# projekt.net
KiCad netlist of a schematic drawn in EAGLE
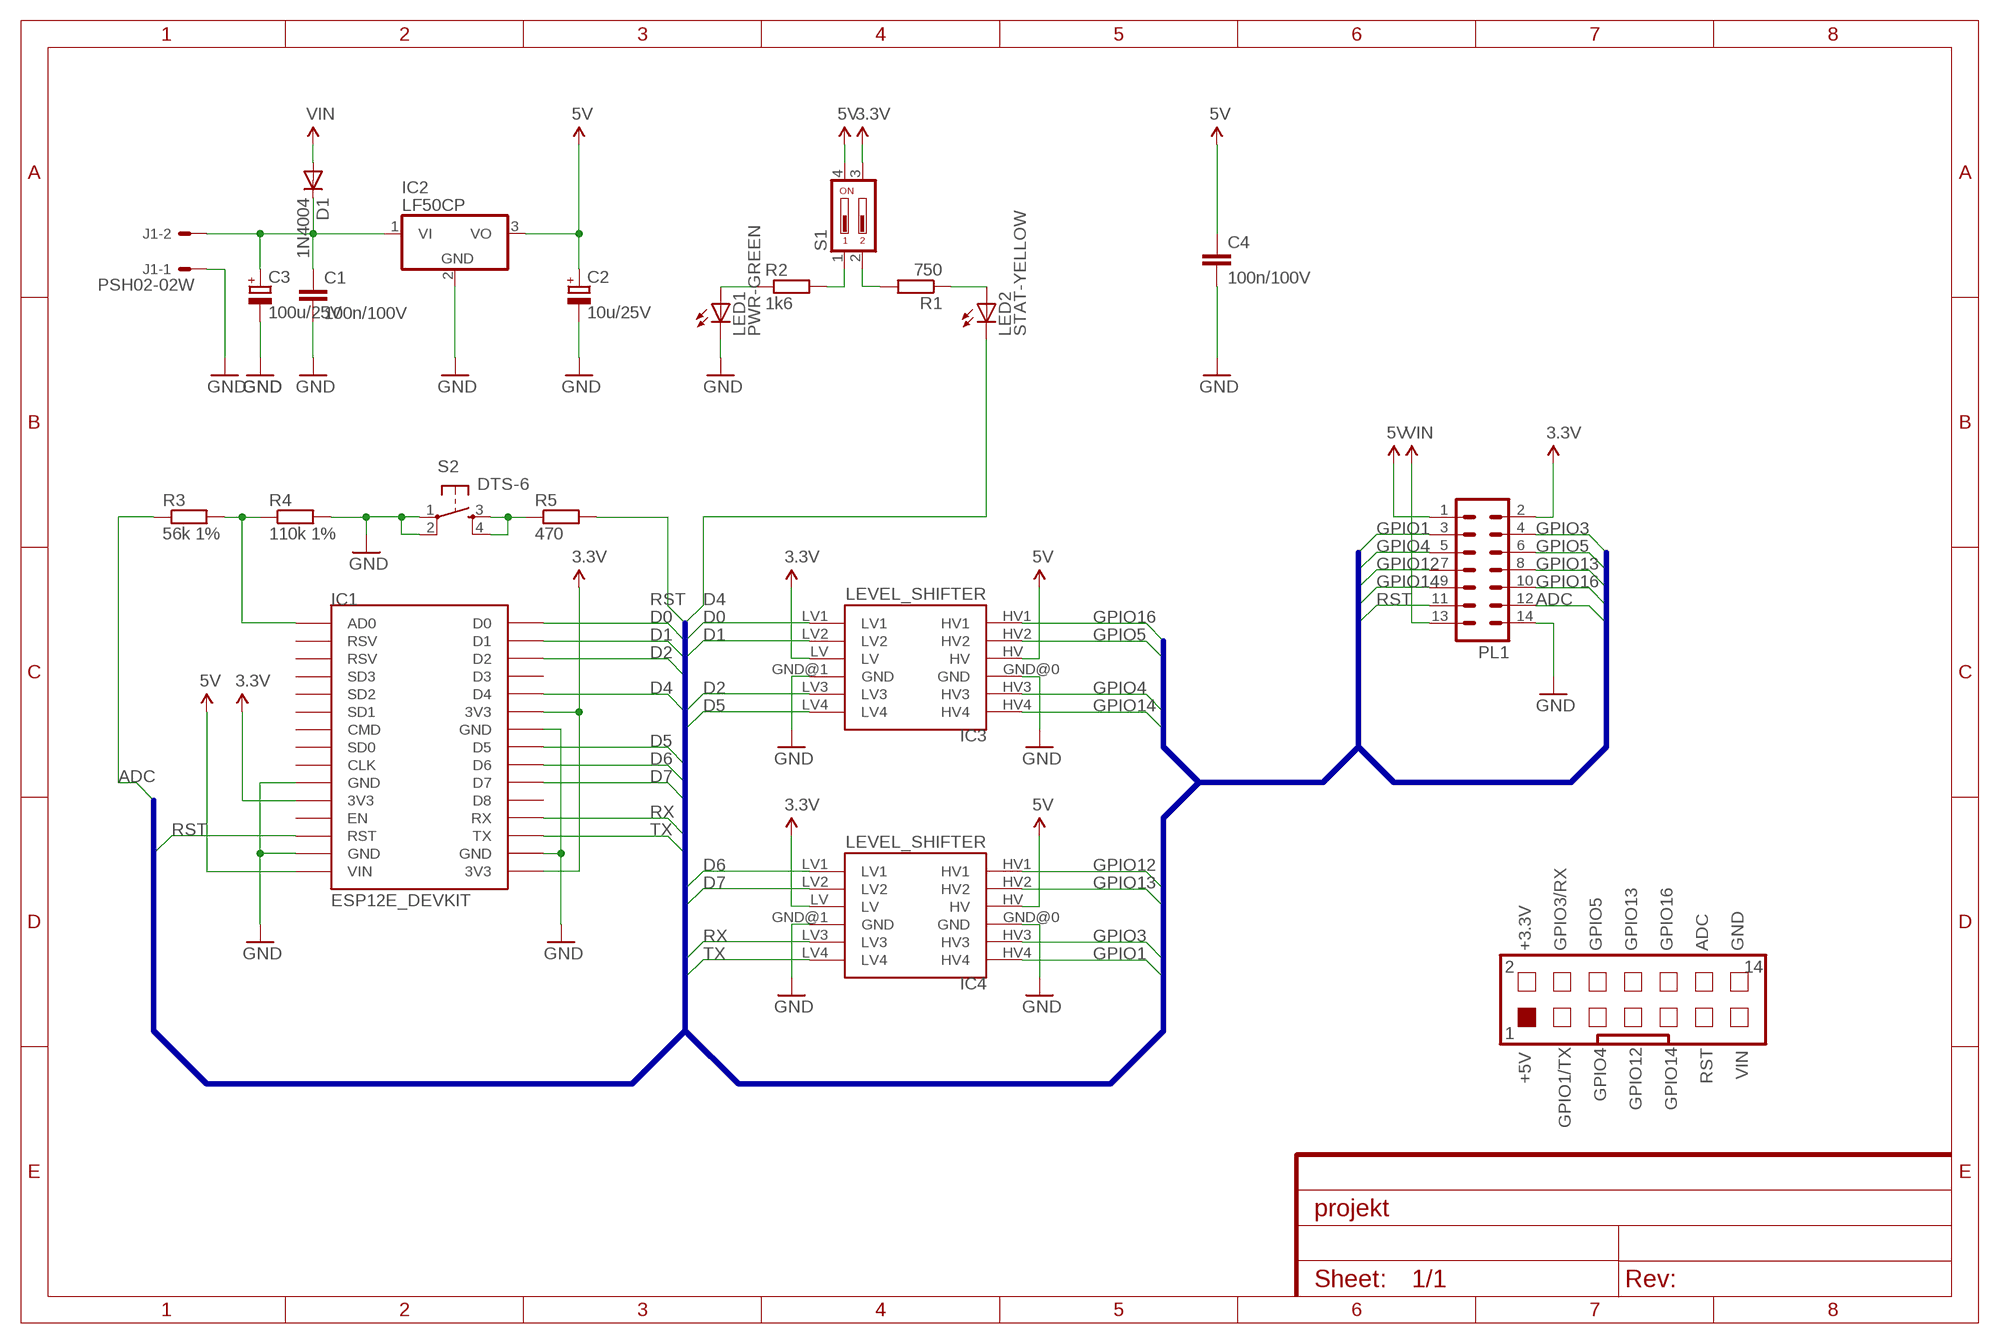
[diagram p0: schematic, sheet 1]

(export (version "E")
  (design (tool "Eeschema 10.0.6"))
  (components
    (comp (ref "C1")
      (value "100n/100V")
      (footprint "eagle-import:C025-025X050")
      (libsource (lib "eagle-import") (part "C-EUC025-025X050"))
    )
    (comp (ref "C2")
      (value "10u/25V")
      (footprint "eagle-import:E3,5-8")
      (libsource (lib "eagle-import") (part "CPOL-EUE3,5-8"))
    )
    (comp (ref "C3")
      (value "100u/25V")
      (footprint "eagle-import:E5-13")
      (libsource (lib "eagle-import") (part "CPOL-EUE5-13"))
    )
    (comp (ref "C4")
      (value "100n/100V")
      (footprint "eagle-import:C025-025X050")
      (libsource (lib "eagle-import") (part "C-EUC025-025X050"))
    )
    (comp (ref "D1")
      (value "1N4004")
      (footprint "eagle-import:DO41-10")
      (libsource (lib "eagle-import") (part "1N4004"))
    )
    (comp (ref "IC1")
      (value "ESP12E_DEVKIT")
      (footprint "eagle-import:ESP12E_DEVKIT")
      (libsource (lib "eagle-import") (part "ESP12E_DEVKIT"))
    )
    (comp (ref "IC2")
      (value "LF50CP")
      (footprint "eagle-import:TO220H")
      (libsource (lib "eagle-import") (part "LF50CP"))
    )
    (comp (ref "IC3")
      (value "LEVEL_SHIFTER")
      (footprint "eagle-import:LEVEL_SHIFTER")
      (libsource (lib "eagle-import") (part "LEVEL_SHIFTER"))
    )
    (comp (ref "IC4")
      (value "LEVEL_SHIFTER")
      (footprint "eagle-import:LEVEL_SHIFTER")
      (libsource (lib "eagle-import") (part "LEVEL_SHIFTER"))
    )
    (comp (ref "J1")
      (value "PSH02-02W")
      (footprint "eagle-import:7395-02")
      (libsource (lib "eagle-import") (part "22-?-0205-7028"))
    )
    (comp (ref "LED1")
      (value "PWR-GREEN")
      (footprint "eagle-import:LED3MM")
      (libsource (lib "eagle-import") (part "LED3MM"))
    )
    (comp (ref "LED2")
      (value "STAT-YELLOW")
      (footprint "eagle-import:LED3MM")
      (libsource (lib "eagle-import") (part "LED3MM"))
    )
    (comp (ref "PL1")
      (value "14H")
      (footprint "eagle-import:14H")
      (libsource (lib "eagle-import") (part "14H"))
    )
    (comp (ref "R1")
      (value "750")
      (footprint "eagle-import:R1206")
      (libsource (lib "eagle-import") (part "R-EU_R1206"))
    )
    (comp (ref "R2")
      (value "1k6")
      (footprint "eagle-import:R1206")
      (libsource (lib "eagle-import") (part "R-EU_R1206"))
    )
    (comp (ref "R3")
      (value "56k 1%")
      (footprint "eagle-import:R1206")
      (libsource (lib "eagle-import") (part "R-EU_R1206"))
    )
    (comp (ref "R4")
      (value "110k 1%")
      (footprint "eagle-import:R1206")
      (libsource (lib "eagle-import") (part "R-EU_R1206"))
    )
    (comp (ref "R5")
      (value "470")
      (footprint "eagle-import:R1206")
      (libsource (lib "eagle-import") (part "R-EU_R1206"))
    )
    (comp (ref "S1")
      (value "DIP02YL")
      (footprint "eagle-import:DIP02YL")
      (libsource (lib "eagle-import") (part "DIP02YL"))
    )
    (comp (ref "S2")
      (value "DTS-6")
      (footprint "eagle-import:DTS-6")
      (libsource (lib "eagle-import") (part "DTS-6"))
    )
  )
  (nets
    (net (code "1") (name "/ADC") (class "Default")
      (node (ref "PL1") (pin "12") (pinfunction "12_12") (pintype "passive"))
      (node (ref "R3") (pin "1") (pinfunction "1_1") (pintype "passive"))
    )
    (net (code "2") (name "/D0") (class "Default")
      (node (ref "IC1") (pin "D0") (pinfunction "D0_D0") (pintype "bidirectional"))
      (node (ref "IC3") (pin "LV1") (pinfunction "LV1_LV1") (pintype "bidirectional"))
    )
    (net (code "3") (name "/D1") (class "Default")
      (node (ref "IC1") (pin "D1") (pinfunction "D1_D1") (pintype "bidirectional"))
      (node (ref "IC3") (pin "LV2") (pinfunction "LV2_LV2") (pintype "bidirectional"))
    )
    (net (code "4") (name "/D2") (class "Default")
      (node (ref "IC1") (pin "D2") (pinfunction "D2_D2") (pintype "bidirectional"))
      (node (ref "IC3") (pin "LV3") (pinfunction "LV3_LV3") (pintype "bidirectional"))
    )
    (net (code "5") (name "/D4") (class "Default")
      (node (ref "IC1") (pin "D4") (pinfunction "D4_D4") (pintype "bidirectional"))
      (node (ref "LED2") (pin "K") (pinfunction "C_K") (pintype "passive"))
    )
    (net (code "6") (name "/D5") (class "Default")
      (node (ref "IC1") (pin "D5") (pinfunction "D5_D5") (pintype "bidirectional"))
      (node (ref "IC3") (pin "LV4") (pinfunction "LV4_LV4") (pintype "bidirectional"))
    )
    (net (code "7") (name "/D6") (class "Default")
      (node (ref "IC1") (pin "D6") (pinfunction "D6_D6") (pintype "bidirectional"))
      (node (ref "IC4") (pin "LV1") (pinfunction "LV1_LV1") (pintype "bidirectional"))
    )
    (net (code "8") (name "/D7") (class "Default")
      (node (ref "IC1") (pin "D7") (pinfunction "D7_D7") (pintype "bidirectional"))
      (node (ref "IC4") (pin "LV2") (pinfunction "LV2_LV2") (pintype "bidirectional"))
    )
    (net (code "9") (name "/GPIO1") (class "Default")
      (node (ref "IC4") (pin "HV4") (pinfunction "HV4_HV4") (pintype "bidirectional"))
      (node (ref "PL1") (pin "3") (pinfunction "3_3") (pintype "passive"))
    )
    (net (code "10") (name "/GPIO3") (class "Default")
      (node (ref "IC4") (pin "HV3") (pinfunction "HV3_HV3") (pintype "bidirectional"))
      (node (ref "PL1") (pin "4") (pinfunction "4_4") (pintype "passive"))
    )
    (net (code "11") (name "/GPIO4") (class "Default")
      (node (ref "IC3") (pin "HV3") (pinfunction "HV3_HV3") (pintype "bidirectional"))
      (node (ref "PL1") (pin "5") (pinfunction "5_5") (pintype "passive"))
    )
    (net (code "12") (name "/GPIO5") (class "Default")
      (node (ref "IC3") (pin "HV2") (pinfunction "HV2_HV2") (pintype "bidirectional"))
      (node (ref "PL1") (pin "6") (pinfunction "6_6") (pintype "passive"))
    )
    (net (code "13") (name "/GPIO12") (class "Default")
      (node (ref "IC4") (pin "HV1") (pinfunction "HV1_HV1") (pintype "bidirectional"))
      (node (ref "PL1") (pin "7") (pinfunction "7_7") (pintype "passive"))
    )
    (net (code "14") (name "/GPIO13") (class "Default")
      (node (ref "IC4") (pin "HV2") (pinfunction "HV2_HV2") (pintype "bidirectional"))
      (node (ref "PL1") (pin "8") (pinfunction "8_8") (pintype "passive"))
    )
    (net (code "15") (name "/GPIO14") (class "Default")
      (node (ref "IC3") (pin "HV4") (pinfunction "HV4_HV4") (pintype "bidirectional"))
      (node (ref "PL1") (pin "9") (pinfunction "9_9") (pintype "passive"))
    )
    (net (code "16") (name "/GPIO16") (class "Default")
      (node (ref "IC3") (pin "HV1") (pinfunction "HV1_HV1") (pintype "bidirectional"))
      (node (ref "PL1") (pin "10") (pinfunction "10_10") (pintype "passive"))
    )
    (net (code "17") (name "/RST") (class "Default")
      (node (ref "IC1") (pin "RST") (pinfunction "RST_RST") (pintype "bidirectional"))
      (node (ref "PL1") (pin "11") (pinfunction "11_11") (pintype "passive"))
      (node (ref "R5") (pin "2") (pinfunction "2_2") (pintype "passive"))
    )
    (net (code "18") (name "/RX") (class "Default")
      (node (ref "IC1") (pin "RX") (pinfunction "RX_RX") (pintype "bidirectional"))
      (node (ref "IC4") (pin "LV3") (pinfunction "LV3_LV3") (pintype "bidirectional"))
    )
    (net (code "19") (name "/TX") (class "Default")
      (node (ref "IC1") (pin "TX") (pinfunction "TX_TX") (pintype "bidirectional"))
      (node (ref "IC4") (pin "LV4") (pinfunction "LV4_LV4") (pintype "bidirectional"))
    )
    (net (code "20") (name "3.3V") (class "Default")
      (node (ref "IC1") (pin "3V3@0") (pinfunction "3V3_3V3@0") (pintype "bidirectional"))
      (node (ref "IC1") (pin "3V3@1") (pinfunction "3V3_3V3@1") (pintype "bidirectional"))
      (node (ref "IC1") (pin "3V3@2") (pinfunction "3V3_3V3@2") (pintype "bidirectional"))
      (node (ref "IC3") (pin "LV") (pinfunction "LV_LV") (pintype "bidirectional"))
      (node (ref "IC4") (pin "LV") (pinfunction "LV_LV") (pintype "bidirectional"))
      (node (ref "PL1") (pin "2") (pinfunction "2_2") (pintype "passive"))
      (node (ref "S1") (pin "3") (pinfunction "3_3") (pintype "passive"))
    )
    (net (code "21") (name "5V") (class "Default")
      (node (ref "C2") (pin "+") (pinfunction "+_+") (pintype "passive"))
      (node (ref "C4") (pin "1") (pinfunction "1_1") (pintype "passive"))
      (node (ref "IC1") (pin "VIN") (pinfunction "VIN_VIN") (pintype "bidirectional"))
      (node (ref "IC2") (pin "3") (pinfunction "VO_3") (pintype "passive"))
      (node (ref "IC3") (pin "HV") (pinfunction "HV_HV") (pintype "bidirectional"))
      (node (ref "IC4") (pin "HV") (pinfunction "HV_HV") (pintype "bidirectional"))
      (node (ref "PL1") (pin "1") (pinfunction "1_1") (pintype "passive"))
      (node (ref "S1") (pin "4") (pinfunction "4_4") (pintype "passive"))
    )
    (net (code "22") (name "GND") (class "Default")
      (node (ref "C1") (pin "2") (pinfunction "2_2") (pintype "passive"))
      (node (ref "C2") (pin "-") (pinfunction "-_-") (pintype "passive"))
      (node (ref "C3") (pin "-") (pinfunction "-_-") (pintype "passive"))
      (node (ref "C4") (pin "2") (pinfunction "2_2") (pintype "passive"))
      (node (ref "IC1") (pin "GND@0") (pinfunction "GND_GND@0") (pintype "bidirectional"))
      (node (ref "IC1") (pin "GND@1") (pinfunction "GND_GND@1") (pintype "bidirectional"))
      (node (ref "IC1") (pin "GND@2") (pinfunction "GND_GND@2") (pintype "bidirectional"))
      (node (ref "IC1") (pin "GND@3") (pinfunction "GND_GND@3") (pintype "bidirectional"))
      (node (ref "IC2") (pin "2") (pinfunction "GND_2") (pintype "passive"))
      (node (ref "IC3") (pin "GND@0") (pinfunction "GND_GND@0") (pintype "bidirectional"))
      (node (ref "IC3") (pin "GND@1") (pinfunction "GND_GND@1") (pintype "bidirectional"))
      (node (ref "IC4") (pin "GND@0") (pinfunction "GND_GND@0") (pintype "bidirectional"))
      (node (ref "IC4") (pin "GND@1") (pinfunction "GND_GND@1") (pintype "bidirectional"))
      (node (ref "J1") (pin "1") (pinfunction "S_1") (pintype "passive"))
      (node (ref "LED1") (pin "K") (pinfunction "C_K") (pintype "passive"))
      (node (ref "PL1") (pin "14") (pinfunction "14_14") (pintype "passive"))
      (node (ref "R4") (pin "2") (pinfunction "2_2") (pintype "passive"))
      (node (ref "S2") (pin "1") (pinfunction "1_1") (pintype "passive"))
      (node (ref "S2") (pin "2") (pinfunction "2_2") (pintype "passive"))
    )
    (net (code "23") (name "Net-(IC1-PadAD0)") (class "Default")
      (node (ref "IC1") (pin "AD0") (pinfunction "AD0_AD0") (pintype "bidirectional"))
      (node (ref "R3") (pin "2") (pinfunction "2_2") (pintype "passive"))
      (node (ref "R4") (pin "1") (pinfunction "1_1") (pintype "passive"))
    )
    (net (code "24") (name "Net-(IC2-VI)") (class "Default")
      (node (ref "C1") (pin "1") (pinfunction "1_1") (pintype "passive"))
      (node (ref "C3") (pin "+") (pinfunction "+_+") (pintype "passive"))
      (node (ref "D1") (pin "C") (pinfunction "C_C") (pintype "passive"))
      (node (ref "IC2") (pin "1") (pinfunction "VI_1") (pintype "input"))
      (node (ref "J1") (pin "2") (pinfunction "S_2") (pintype "passive"))
    )
    (net (code "25") (name "Net-(LED1-PadA)") (class "Default")
      (node (ref "LED1") (pin "A") (pinfunction "A_A") (pintype "passive"))
      (node (ref "R2") (pin "1") (pinfunction "1_1") (pintype "passive"))
    )
    (net (code "26") (name "Net-(LED2-PadA)") (class "Default")
      (node (ref "LED2") (pin "A") (pinfunction "A_A") (pintype "passive"))
      (node (ref "R1") (pin "1") (pinfunction "1_1") (pintype "passive"))
    )
    (net (code "27") (name "Net-(R1-Pad2)") (class "Default")
      (node (ref "R1") (pin "2") (pinfunction "2_2") (pintype "passive"))
      (node (ref "S1") (pin "2") (pinfunction "2_2") (pintype "passive"))
    )
    (net (code "28") (name "Net-(R2-Pad2)") (class "Default")
      (node (ref "R2") (pin "2") (pinfunction "2_2") (pintype "passive"))
      (node (ref "S1") (pin "1") (pinfunction "1_1") (pintype "passive"))
    )
    (net (code "29") (name "Net-(R5-Pad1)") (class "Default")
      (node (ref "R5") (pin "1") (pinfunction "1_1") (pintype "passive"))
      (node (ref "S2") (pin "3") (pinfunction "3_3") (pintype "passive"))
      (node (ref "S2") (pin "4") (pinfunction "4_4") (pintype "passive"))
    )
    (net (code "30") (name "VIN") (class "Default")
      (node (ref "D1") (pin "A") (pinfunction "A_A") (pintype "passive"))
      (node (ref "PL1") (pin "13") (pinfunction "13_13") (pintype "passive"))
    )
    (net (code "31") (name "unconnected-(IC1-PadCLK)") (class "Default")
      (node (ref "IC1") (pin "CLK") (pinfunction "CLK_CLK") (pintype "bidirectional"))
    )
    (net (code "32") (name "unconnected-(IC1-PadCMD)") (class "Default")
      (node (ref "IC1") (pin "CMD") (pinfunction "CMD_CMD") (pintype "bidirectional"))
    )
    (net (code "33") (name "unconnected-(IC1-PadD3)") (class "Default")
      (node (ref "IC1") (pin "D3") (pinfunction "D3_D3") (pintype "bidirectional"))
    )
    (net (code "34") (name "unconnected-(IC1-PadD8)") (class "Default")
      (node (ref "IC1") (pin "D8") (pinfunction "D8_D8") (pintype "bidirectional"))
    )
    (net (code "35") (name "unconnected-(IC1-PadEN)") (class "Default")
      (node (ref "IC1") (pin "EN") (pinfunction "EN_EN") (pintype "bidirectional"))
    )
    (net (code "36") (name "unconnected-(IC1-PadSD0)") (class "Default")
      (node (ref "IC1") (pin "SD0") (pinfunction "SD0_SD0") (pintype "bidirectional"))
    )
    (net (code "37") (name "unconnected-(IC1-PadSD1)") (class "Default")
      (node (ref "IC1") (pin "SD1") (pinfunction "SD1_SD1") (pintype "bidirectional"))
    )
    (net (code "38") (name "unconnected-(IC1-PadSD2)") (class "Default")
      (node (ref "IC1") (pin "SD2") (pinfunction "SD2_SD2") (pintype "bidirectional"))
    )
    (net (code "39") (name "unconnected-(IC1-PadSD3)") (class "Default")
      (node (ref "IC1") (pin "SD3") (pinfunction "SD3_SD3") (pintype "bidirectional"))
    )
    (net (code "40") (name "unconnected-(IC1-RSV-PadRSV@0)") (class "Default")
      (node (ref "IC1") (pin "RSV@0") (pinfunction "RSV_RSV@0") (pintype "bidirectional"))
    )
    (net (code "41") (name "unconnected-(IC1-RSV-PadRSV@1)") (class "Default")
      (node (ref "IC1") (pin "RSV@1") (pinfunction "RSV_RSV@1") (pintype "bidirectional"))
    )
  )
)
